# LB_BIT_i20_SOUNDTRIGGER-v03_rev1.net
KiCad netlist of a schematic drawn in EAGLE
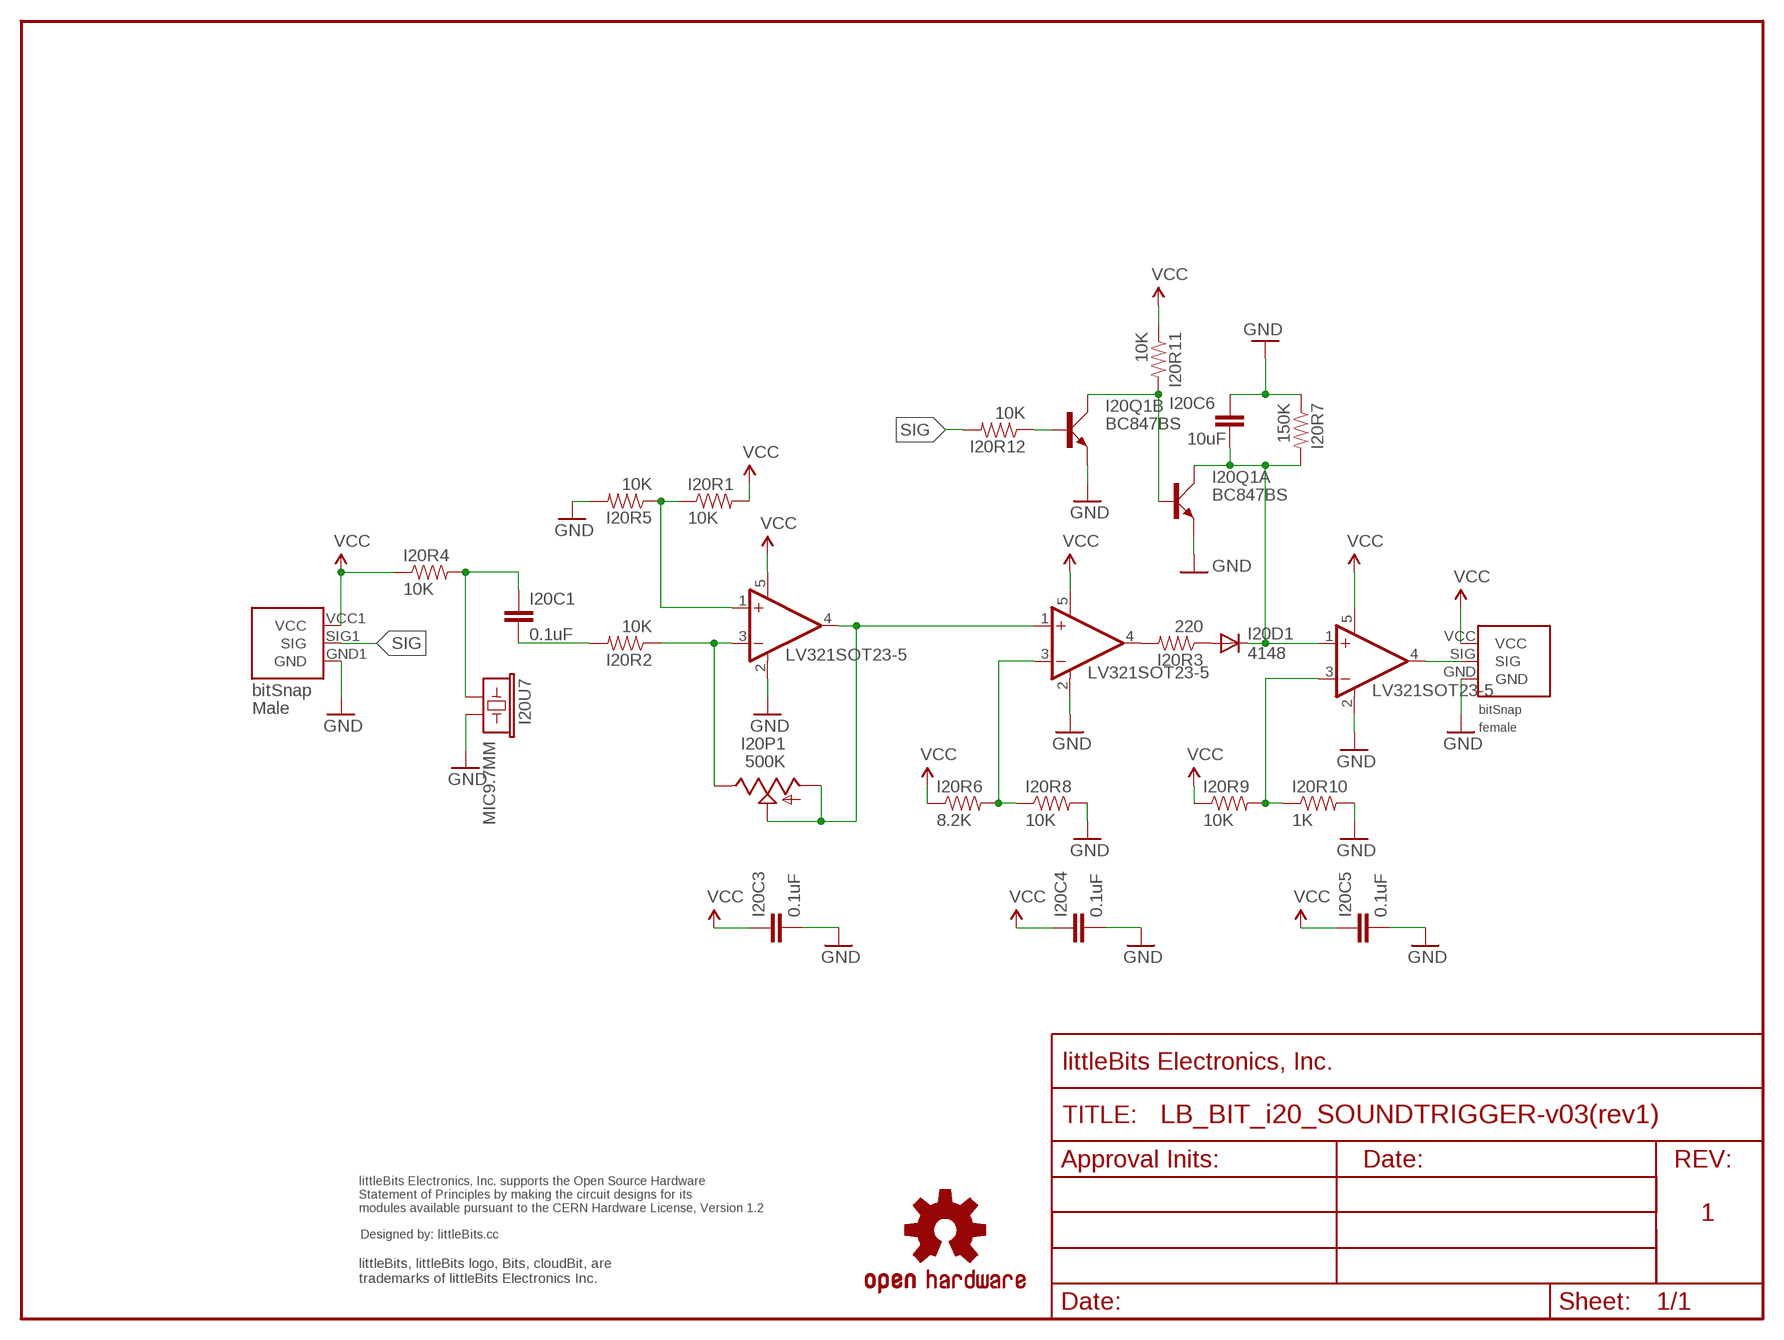
[diagram p0: schematic, sheet 1]

(export (version "E")
  (design (tool "Eeschema 10.0.6"))
  (components
    (comp (ref "I20BSF1")
      (value "BITSNAP_V03_FEMALE")
      (footprint "eagle-import:BITSNAP_V03_FEMALE")
      (libsource (lib "eagle-import") (part "BITSNAP_V03_FEMALE"))
    )
    (comp (ref "I20BSM1")
      (value "BITSNAP_V03_MALE")
      (footprint "eagle-import:BITSNAP_V03_MALE")
      (libsource (lib "eagle-import") (part "BITSNAP_V03_MALE"))
    )
    (comp (ref "I20C1")
      (value "0.1uF")
      (footprint "eagle-import:0603-CAP")
      (libsource (lib "eagle-import") (part "CAP0603-CAP"))
    )
    (comp (ref "I20C3")
      (value "0.1uF")
      (footprint "eagle-import:0603-CAP")
      (libsource (lib "eagle-import") (part "CAP0603-CAP"))
    )
    (comp (ref "I20C4")
      (value "0.1uF")
      (footprint "eagle-import:0603-CAP")
      (libsource (lib "eagle-import") (part "CAP0603-CAP"))
    )
    (comp (ref "I20C5")
      (value "0.1uF")
      (footprint "eagle-import:0603-CAP")
      (libsource (lib "eagle-import") (part "CAP0603-CAP"))
    )
    (comp (ref "I20C6")
      (value "10uF")
      (footprint "eagle-import:0805")
      (libsource (lib "eagle-import") (part "CAP0805"))
    )
    (comp (ref "I20D1")
      (value "4148")
      (footprint "eagle-import:SOD-323")
      (libsource (lib "eagle-import") (part "DIODESOD"))
    )
    (comp (ref "I20P1")
      (value "500K")
      (footprint "eagle-import:POT-TRIM-SMD-BOURNS-3303")
      (libsource (lib "eagle-import") (part "POT-TRIM-SMD-BOURNS-3303"))
    )
    (comp (ref "I20Q1")
      (value "BC847BS")
      (footprint "eagle-import:SOT363_PHILIPS")
      (libsource (lib "eagle-import") (part "BC847BS"))
    )
    (comp (ref "I20R1")
      (value "10K")
      (footprint "eagle-import:0603-RES")
      (libsource (lib "eagle-import") (part "RESISTOR0603-RES"))
    )
    (comp (ref "I20R2")
      (value "10K")
      (footprint "eagle-import:0603-RES")
      (libsource (lib "eagle-import") (part "RESISTOR0603-RES"))
    )
    (comp (ref "I20R3")
      (value "220")
      (footprint "eagle-import:0603-RES")
      (libsource (lib "eagle-import") (part "RESISTOR0603-RES"))
    )
    (comp (ref "I20R4")
      (value "10K")
      (footprint "eagle-import:0603-RES")
      (libsource (lib "eagle-import") (part "RESISTOR0603-RES"))
    )
    (comp (ref "I20R5")
      (value "10K")
      (footprint "eagle-import:0603-RES")
      (libsource (lib "eagle-import") (part "RESISTOR0603-RES"))
    )
    (comp (ref "I20R6")
      (value "8.2K")
      (footprint "eagle-import:0603-RES")
      (libsource (lib "eagle-import") (part "RESISTOR0603-RES"))
    )
    (comp (ref "I20R7")
      (value "150K")
      (footprint "eagle-import:0603-RES")
      (libsource (lib "eagle-import") (part "RESISTOR0603-RES"))
    )
    (comp (ref "I20R8")
      (value "10K")
      (footprint "eagle-import:0603-RES")
      (libsource (lib "eagle-import") (part "RESISTOR0603-RES"))
    )
    (comp (ref "I20R9")
      (value "10K")
      (footprint "eagle-import:0603-RES")
      (libsource (lib "eagle-import") (part "RESISTOR0603-RES"))
    )
    (comp (ref "I20R10")
      (value "1K")
      (footprint "eagle-import:0603-RES")
      (libsource (lib "eagle-import") (part "RESISTOR0603-RES"))
    )
    (comp (ref "I20R11")
      (value "10K")
      (footprint "eagle-import:0603-RES")
      (libsource (lib "eagle-import") (part "RESISTOR0603-RES"))
    )
    (comp (ref "I20R12")
      (value "10K")
      (footprint "eagle-import:0603-RES")
      (libsource (lib "eagle-import") (part "RESISTOR0603-RES"))
    )
    (comp (ref "I20U1")
      (value "LV321SOT23-5")
      (footprint "eagle-import:SOT23-5")
      (libsource (lib "eagle-import") (part "LV321SOT23-5"))
    )
    (comp (ref "I20U2")
      (value "LV321SOT23-5")
      (footprint "eagle-import:SOT23-5")
      (libsource (lib "eagle-import") (part "LV321SOT23-5"))
    )
    (comp (ref "I20U3")
      (value "LV321SOT23-5")
      (footprint "eagle-import:SOT23-5")
      (libsource (lib "eagle-import") (part "LV321SOT23-5"))
    )
    (comp (ref "I20U7")
      (value "MIC9.7MM")
      (footprint "eagle-import:MIC-9.7MM")
      (libsource (lib "eagle-import") (part "MIC9.7MM"))
    )
    (comp (ref "U$1")
      (value "OSHWCREDIT")
      (footprint "eagle-import:OSHWCREDIT")
      (libsource (lib "eagle-import") (part "OSHWCREDIT"))
    )
    (comp (ref "U$5")
      (value "FRAME-LETTER-OHWOHW")
      (footprint "eagle-import:FABDWG01-OHW")
      (libsource (lib "eagle-import") (part "FRAME-LETTER-OHWOHW"))
    )
    (comp (ref "U$29")
      (value "OSHW-LOGOL")
      (footprint "eagle-import:OSHW-LOGO-L")
      (libsource (lib "eagle-import") (part "OSHW-LOGOL"))
    )
  )
  (nets
    (net (code "1") (name "GND") (class "Default")
      (node (ref "I20BSF1") (pin "GND") (pinfunction "GND_GND") (pintype "bidirectional"))
      (node (ref "I20BSM1") (pin "GND1") (pinfunction "GND_GND1") (pintype "bidirectional"))
      (node (ref "I20C3") (pin "2") (pinfunction "2_2") (pintype "passive"))
      (node (ref "I20C4") (pin "2") (pinfunction "2_2") (pintype "passive"))
      (node (ref "I20C5") (pin "2") (pinfunction "2_2") (pintype "passive"))
      (node (ref "I20C6") (pin "1") (pinfunction "1_1") (pintype "passive"))
      (node (ref "I20Q1") (pin "1") (pinfunction "E_1") (pintype "passive"))
      (node (ref "I20Q1") (pin "4") (pinfunction "E_4") (pintype "passive"))
      (node (ref "I20R10") (pin "2") (pinfunction "2_2") (pintype "passive"))
      (node (ref "I20R5") (pin "2") (pinfunction "2_2") (pintype "passive"))
      (node (ref "I20R7") (pin "1") (pinfunction "1_1") (pintype "passive"))
      (node (ref "I20R8") (pin "2") (pinfunction "2_2") (pintype "passive"))
      (node (ref "I20U1") (pin "2") (pinfunction "V-_2") (pintype "power_in"))
      (node (ref "I20U2") (pin "2") (pinfunction "V-_2") (pintype "power_in"))
      (node (ref "I20U3") (pin "2") (pinfunction "V-_2") (pintype "power_in"))
      (node (ref "I20U7") (pin "2") (pinfunction "2_2") (pintype "passive"))
    )
    (net (code "2") (name "Net-(I20C1-Pad1)") (class "Default")
      (node (ref "I20C1") (pin "1") (pinfunction "1_1") (pintype "passive"))
      (node (ref "I20R4") (pin "2") (pinfunction "2_2") (pintype "passive"))
      (node (ref "I20U7") (pin "1") (pinfunction "1_1") (pintype "passive"))
    )
    (net (code "3") (name "Net-(I20C1-Pad2)") (class "Default")
      (node (ref "I20C1") (pin "2") (pinfunction "2_2") (pintype "passive"))
      (node (ref "I20R2") (pin "2") (pinfunction "2_2") (pintype "passive"))
    )
    (net (code "4") (name "Net-(I20D1-A)") (class "Default")
      (node (ref "I20D1") (pin "2") (pinfunction "A_2") (pintype "passive"))
      (node (ref "I20R3") (pin "1") (pinfunction "1_1") (pintype "passive"))
    )
    (net (code "5") (name "Net-(I20D1-C)") (class "Default")
      (node (ref "I20C6") (pin "2") (pinfunction "2_2") (pintype "passive"))
      (node (ref "I20D1") (pin "1") (pinfunction "C_1") (pintype "passive"))
      (node (ref "I20Q1") (pin "6") (pinfunction "C_6") (pintype "passive"))
      (node (ref "I20R7") (pin "2") (pinfunction "2_2") (pintype "passive"))
      (node (ref "I20U3") (pin "1") (pinfunction "+IN_1") (pintype "input"))
    )
    (net (code "6") (name "Net-(I20P1-A)") (class "Default")
      (node (ref "I20P1") (pin "1") (pinfunction "A_1") (pintype "passive"))
      (node (ref "I20P1") (pin "2") (pinfunction "S_2") (pintype "passive"))
      (node (ref "I20U1") (pin "4") (pinfunction "OUT_4") (pintype "output"))
      (node (ref "I20U2") (pin "1") (pinfunction "+IN_1") (pintype "input"))
    )
    (net (code "7") (name "Net-(I20P1-E)") (class "Default")
      (node (ref "I20P1") (pin "3") (pinfunction "E_3") (pintype "passive"))
      (node (ref "I20R2") (pin "1") (pinfunction "1_1") (pintype "passive"))
      (node (ref "I20U1") (pin "3") (pinfunction "-IN_3") (pintype "input"))
    )
    (net (code "8") (name "Net-(I20Q1A-B)") (class "Default")
      (node (ref "I20Q1") (pin "2") (pinfunction "B_2") (pintype "passive"))
      (node (ref "I20Q1") (pin "3") (pinfunction "C_3") (pintype "passive"))
      (node (ref "I20R11") (pin "2") (pinfunction "2_2") (pintype "passive"))
    )
    (net (code "9") (name "Net-(I20Q1B-B)") (class "Default")
      (node (ref "I20Q1") (pin "5") (pinfunction "B_5") (pintype "passive"))
      (node (ref "I20R12") (pin "1") (pinfunction "1_1") (pintype "passive"))
    )
    (net (code "10") (name "Net-(I20U1-+IN)") (class "Default")
      (node (ref "I20R1") (pin "1") (pinfunction "1_1") (pintype "passive"))
      (node (ref "I20R5") (pin "1") (pinfunction "1_1") (pintype "passive"))
      (node (ref "I20U1") (pin "1") (pinfunction "+IN_1") (pintype "input"))
    )
    (net (code "11") (name "Net-(I20U2--IN)") (class "Default")
      (node (ref "I20R6") (pin "2") (pinfunction "2_2") (pintype "passive"))
      (node (ref "I20R8") (pin "1") (pinfunction "1_1") (pintype "passive"))
      (node (ref "I20U2") (pin "3") (pinfunction "-IN_3") (pintype "input"))
    )
    (net (code "12") (name "Net-(I20U2-OUT)") (class "Default")
      (node (ref "I20R3") (pin "2") (pinfunction "2_2") (pintype "passive"))
      (node (ref "I20U2") (pin "4") (pinfunction "OUT_4") (pintype "output"))
    )
    (net (code "13") (name "Net-(I20U3--IN)") (class "Default")
      (node (ref "I20R10") (pin "1") (pinfunction "1_1") (pintype "passive"))
      (node (ref "I20R9") (pin "2") (pinfunction "2_2") (pintype "passive"))
      (node (ref "I20U3") (pin "3") (pinfunction "-IN_3") (pintype "input"))
    )
    (net (code "14") (name "Net-(I20U3-OUT)") (class "Default")
      (node (ref "I20BSF1") (pin "SIG") (pinfunction "SIG_SIG") (pintype "bidirectional"))
      (node (ref "I20U3") (pin "4") (pinfunction "OUT_4") (pintype "output"))
    )
    (net (code "15") (name "SIG") (class "Default")
      (node (ref "I20BSM1") (pin "SIG1") (pinfunction "SIG_SIG1") (pintype "bidirectional"))
      (node (ref "I20R12") (pin "2") (pinfunction "2_2") (pintype "passive"))
    )
    (net (code "16") (name "VCC") (class "Default")
      (node (ref "I20BSF1") (pin "VCC") (pinfunction "VCC_VCC") (pintype "bidirectional"))
      (node (ref "I20BSM1") (pin "VCC1") (pinfunction "VCC_VCC1") (pintype "bidirectional"))
      (node (ref "I20C3") (pin "1") (pinfunction "1_1") (pintype "passive"))
      (node (ref "I20C4") (pin "1") (pinfunction "1_1") (pintype "passive"))
      (node (ref "I20C5") (pin "1") (pinfunction "1_1") (pintype "passive"))
      (node (ref "I20R1") (pin "2") (pinfunction "2_2") (pintype "passive"))
      (node (ref "I20R11") (pin "1") (pinfunction "1_1") (pintype "passive"))
      (node (ref "I20R4") (pin "1") (pinfunction "1_1") (pintype "passive"))
      (node (ref "I20R6") (pin "1") (pinfunction "1_1") (pintype "passive"))
      (node (ref "I20R9") (pin "1") (pinfunction "1_1") (pintype "passive"))
      (node (ref "I20U1") (pin "5") (pinfunction "V+_5") (pintype "power_in"))
      (node (ref "I20U2") (pin "5") (pinfunction "V+_5") (pintype "power_in"))
      (node (ref "I20U3") (pin "5") (pinfunction "V+_5") (pintype "power_in"))
    )
  )
)
